# HotStick.net
KiCad netlist of a schematic drawn in EAGLE
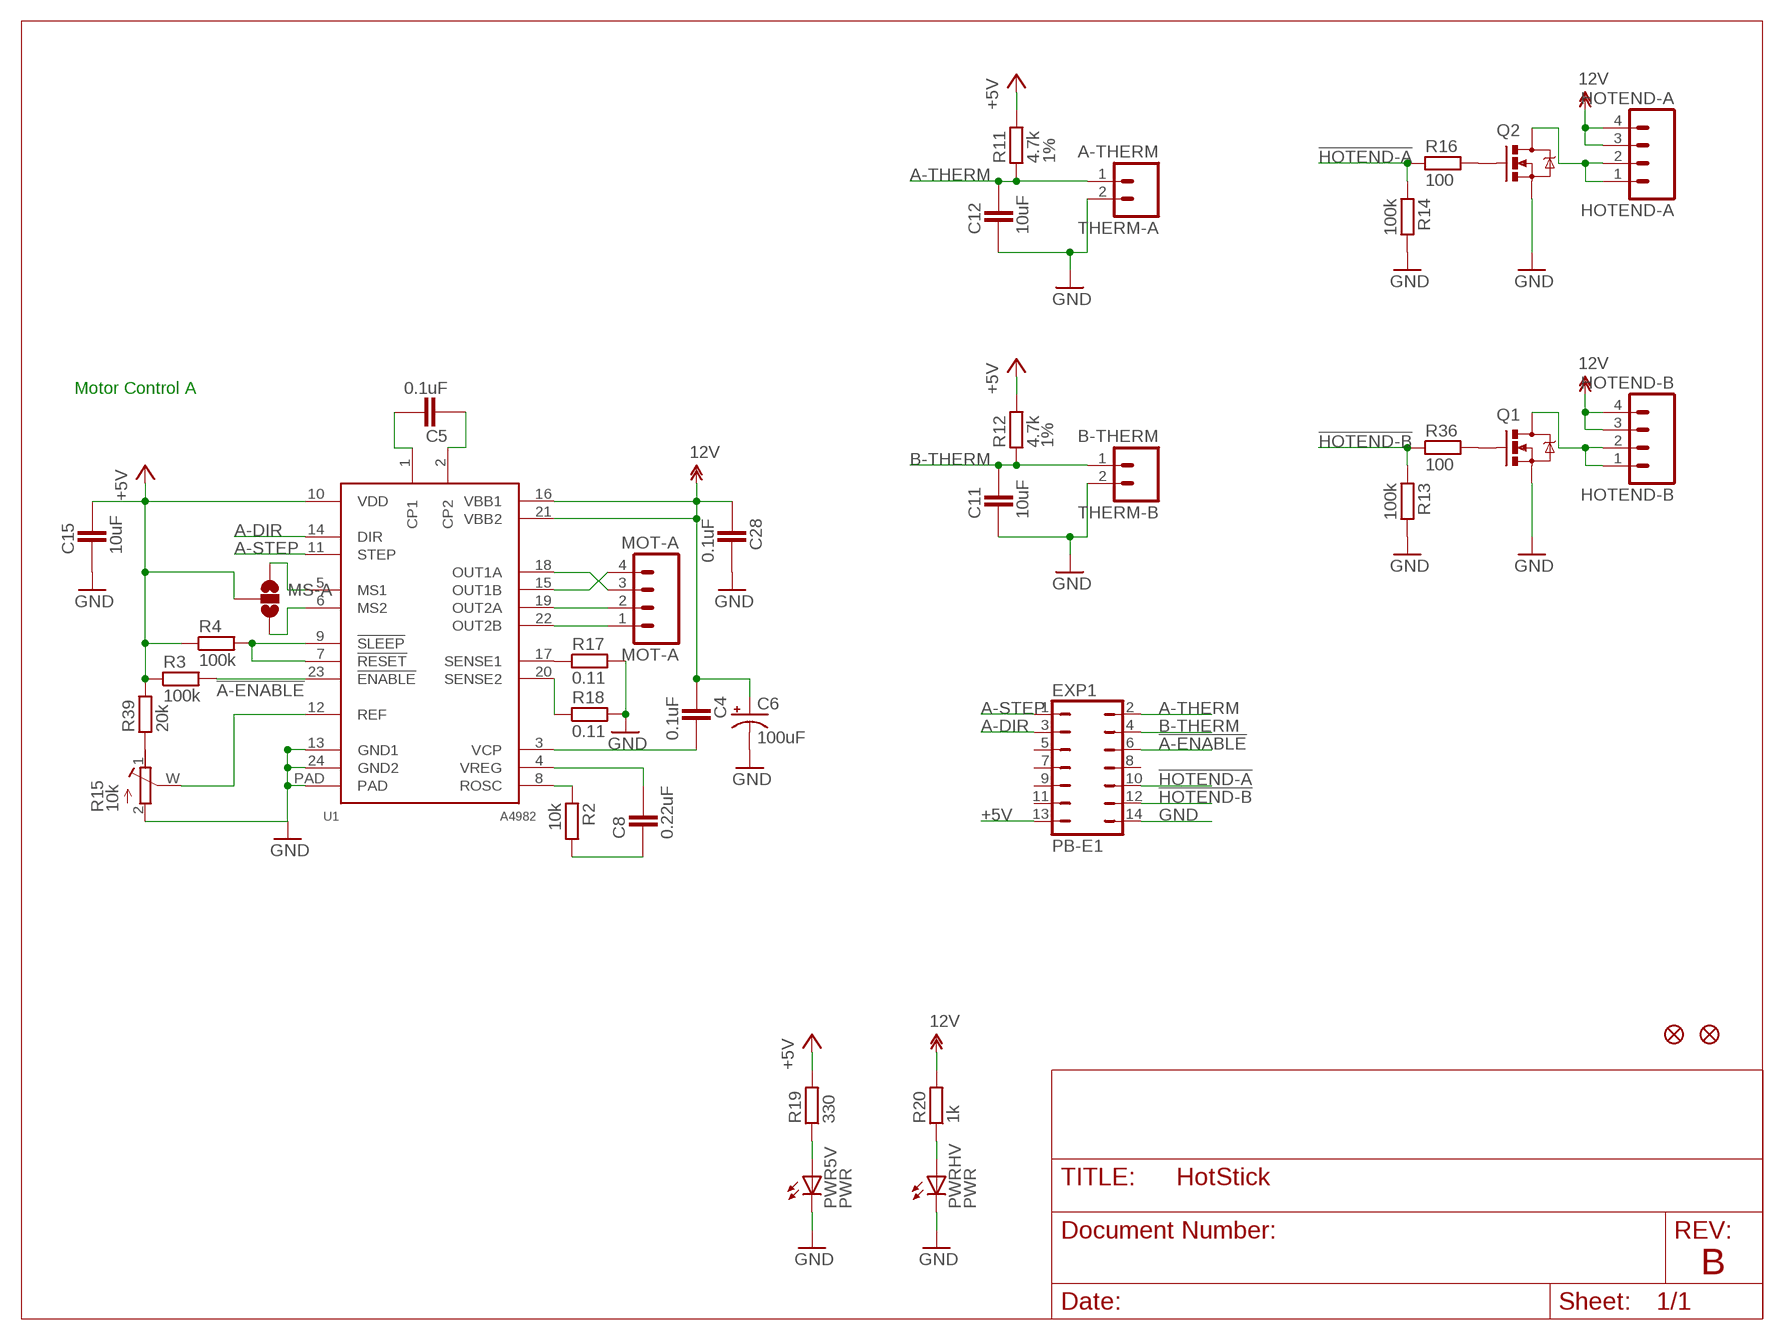
[diagram p0: schematic, sheet 1]

(export (version "E")
  (design (tool "Eeschema 10.0.6"))
  (components
    (comp (ref "C4")
      (value "0.1uF")
      (footprint "eagle-import:CAPC2012X145AN")
      (libsource (lib "eagle-import") (part "CAPACITOR_0805"))
    )
    (comp (ref "C5")
      (value "0.1uF")
      (footprint "eagle-import:CAPC2012X145AN")
      (libsource (lib "eagle-import") (part "CAPACITOR_0805"))
    )
    (comp (ref "C6")
      (value "100uF")
      (footprint "eagle-import:PANASONIC_D")
      (libsource (lib "eagle-import") (part "CPOL-USD"))
    )
    (comp (ref "C8")
      (value "0.22uF")
      (footprint "eagle-import:CAPC2012X145AN")
      (libsource (lib "eagle-import") (part "CAPACITOR_0805"))
    )
    (comp (ref "C11")
      (value "10uF")
      (footprint "eagle-import:CAPC2012X145AN")
      (libsource (lib "eagle-import") (part "CAPACITOR_0805"))
    )
    (comp (ref "C12")
      (value "10uF")
      (footprint "eagle-import:CAPC2012X145AN")
      (libsource (lib "eagle-import") (part "CAPACITOR_0805"))
    )
    (comp (ref "C15")
      (value "10uF")
      (footprint "eagle-import:CAPC2012X145AN")
      (libsource (lib "eagle-import") (part "CAPACITOR_0805"))
    )
    (comp (ref "C28")
      (value "0.1uF")
      (footprint "eagle-import:CAPC2012X145AN")
      (libsource (lib "eagle-import") (part "CAPACITOR_0805"))
    )
    (comp (ref "EXP1")
      (value "PB-E1")
      (footprint "eagle-import:JP7Q")
      (libsource (lib "eagle-import") (part "JP7Q"))
    )
    (comp (ref "HOTEND-A")
      (value "HOTEND-A")
      (footprint "eagle-import:MOLEX-1X4")
      (libsource (lib "eagle-import") (part "M04POLAR"))
    )
    (comp (ref "HOTEND-B")
      (value "HOTEND-B")
      (footprint "eagle-import:MOLEX-1X4")
      (libsource (lib "eagle-import") (part "M04POLAR"))
    )
    (comp (ref "JP1")
      (value "FIDUCIAL1X2.5")
      (footprint "eagle-import:FIDUCIAL-1X2.5")
      (libsource (lib "eagle-import") (part "FIDUCIAL1X2.5"))
    )
    (comp (ref "JP2")
      (value "FIDUCIAL1X2.5")
      (footprint "eagle-import:FIDUCIAL-1X2.5")
      (libsource (lib "eagle-import") (part "FIDUCIAL1X2.5"))
    )
    (comp (ref "MOT-A")
      (value "MOT-A")
      (footprint "eagle-import:MOLEX-1X4")
      (libsource (lib "eagle-import") (part "M04POLAR"))
    )
    (comp (ref "MS-A")
      (value "SOLDERJUMPER_2WAYCONNECTED")
      (footprint "eagle-import:SJ_3_CONNECTED")
      (libsource (lib "eagle-import") (part "SOLDERJUMPER_2WAYCONNECTED"))
    )
    (comp (ref "PWR5V")
      (value "PWR")
      (footprint "eagle-import:CHIP-LED0805")
      (libsource (lib "eagle-import") (part "LEDCHIP-LED0805"))
    )
    (comp (ref "PWRHV")
      (value "PWR")
      (footprint "eagle-import:CHIP-LED0805")
      (libsource (lib "eagle-import") (part "LEDCHIP-LED0805"))
    )
    (comp (ref "Q1")
      (value "MOSFET-NCHANNELPTH2")
      (footprint "eagle-import:TO220V")
      (libsource (lib "eagle-import") (part "MOSFET-NCHANNELPTH2"))
    )
    (comp (ref "Q2")
      (value "MOSFET-NCHANNELPTH2")
      (footprint "eagle-import:TO220V")
      (libsource (lib "eagle-import") (part "MOSFET-NCHANNELPTH2"))
    )
    (comp (ref "R2")
      (value "10k")
      (footprint "eagle-import:RESC2012X70N")
      (libsource (lib "eagle-import") (part "RESISTOR_0805"))
    )
    (comp (ref "R3")
      (value "100k")
      (footprint "eagle-import:RESC2012X70N")
      (libsource (lib "eagle-import") (part "RESISTOR_0805"))
    )
    (comp (ref "R4")
      (value "100k")
      (footprint "eagle-import:RESC2012X70N")
      (libsource (lib "eagle-import") (part "RESISTOR_0805"))
    )
    (comp (ref "R11")
      (value "4.7k")
      (footprint "eagle-import:RESC2012X70N")
      (fields (field (name "TOLERANCE") "1%"))
      (libsource (lib "eagle-import") (part "RESISTOR_0805"))
    )
    (comp (ref "R12")
      (value "4.7k")
      (footprint "eagle-import:RESC2012X70N")
      (fields (field (name "TOLERANCE") "1%"))
      (libsource (lib "eagle-import") (part "RESISTOR_0805"))
    )
    (comp (ref "R13")
      (value "100k")
      (footprint "eagle-import:RESC2012X70N")
      (libsource (lib "eagle-import") (part "RESISTOR_0805"))
    )
    (comp (ref "R14")
      (value "100k")
      (footprint "eagle-import:RESC2012X70N")
      (libsource (lib "eagle-import") (part "RESISTOR_0805"))
    )
    (comp (ref "R15")
      (value "10k")
      (footprint "eagle-import:RTRIM-ST4ETB")
      (libsource (lib "eagle-import") (part "RTRIM-ST-4EA"))
    )
    (comp (ref "R16")
      (value "100")
      (footprint "eagle-import:RESC2012X70N")
      (libsource (lib "eagle-import") (part "RESISTOR_0805"))
    )
    (comp (ref "R17")
      (value "0.11")
      (footprint "eagle-import:RESC2012X70N")
      (libsource (lib "eagle-import") (part "RESISTOR_0805"))
    )
    (comp (ref "R18")
      (value "0.11")
      (footprint "eagle-import:RESC2012X70N")
      (libsource (lib "eagle-import") (part "RESISTOR_0805"))
    )
    (comp (ref "R19")
      (value "330")
      (footprint "eagle-import:RESC2012X70N")
      (libsource (lib "eagle-import") (part "RESISTOR_0805"))
    )
    (comp (ref "R20")
      (value "1k")
      (footprint "eagle-import:RESC2012X70N")
      (libsource (lib "eagle-import") (part "RESISTOR_0805"))
    )
    (comp (ref "R36")
      (value "100")
      (footprint "eagle-import:RESC2012X70N")
      (libsource (lib "eagle-import") (part "RESISTOR_0805"))
    )
    (comp (ref "R39")
      (value "20k")
      (footprint "eagle-import:RESC2012X70N")
      (libsource (lib "eagle-import") (part "RESISTOR_0805"))
    )
    (comp (ref "THERM-A")
      (value "A-THERM")
      (footprint "eagle-import:1X02")
      (libsource (lib "eagle-import") (part "M02PTH"))
    )
    (comp (ref "THERM-B")
      (value "B-THERM")
      (footprint "eagle-import:1X02")
      (libsource (lib "eagle-import") (part "M02PTH"))
    )
    (comp (ref "U1")
      (value "A4982")
      (footprint "eagle-import:TSSOP-24")
      (libsource (lib "eagle-import") (part "A4982"))
    )
  )
  (nets
    (net (code "1") (name "+5V") (class "Default")
      (node (ref "C15") (pin "2") (pinfunction "2_2") (pintype "passive"))
      (node (ref "EXP1") (pin "13") (pinfunction "13_13") (pintype "passive"))
      (node (ref "MS-A") (pin "2") (pinfunction "2_2") (pintype "passive"))
      (node (ref "R11") (pin "2") (pinfunction "2_2") (pintype "passive"))
      (node (ref "R12") (pin "2") (pinfunction "2_2") (pintype "passive"))
      (node (ref "R19") (pin "2") (pinfunction "2_2") (pintype "passive"))
      (node (ref "R3") (pin "1") (pinfunction "1_1") (pintype "passive"))
      (node (ref "R39") (pin "2") (pinfunction "2_2") (pintype "passive"))
      (node (ref "R4") (pin "1") (pinfunction "1_1") (pintype "passive"))
      (node (ref "U1") (pin "10") (pinfunction "VDD_10") (pintype "power_in"))
    )
    (net (code "2") (name "/A-DIR") (class "Default")
      (node (ref "EXP1") (pin "3") (pinfunction "3_3") (pintype "passive"))
      (node (ref "U1") (pin "14") (pinfunction "DIR_14") (pintype "input"))
    )
    (net (code "3") (name "/A-STEP") (class "Default")
      (node (ref "EXP1") (pin "1") (pinfunction "1_1") (pintype "passive"))
      (node (ref "U1") (pin "11") (pinfunction "STEP_11") (pintype "input"))
    )
    (net (code "4") (name "/A-THERM") (class "Default")
      (node (ref "C12") (pin "2") (pinfunction "2_2") (pintype "passive"))
      (node (ref "EXP1") (pin "2") (pinfunction "2_2") (pintype "passive"))
      (node (ref "R11") (pin "1") (pinfunction "1_1") (pintype "passive"))
      (node (ref "THERM-A") (pin "1") (pinfunction "1_1") (pintype "passive"))
    )
    (net (code "5") (name "/B-THERM") (class "Default")
      (node (ref "C11") (pin "2") (pinfunction "2_2") (pintype "passive"))
      (node (ref "EXP1") (pin "4") (pinfunction "4_4") (pintype "passive"))
      (node (ref "R12") (pin "1") (pinfunction "1_1") (pintype "passive"))
      (node (ref "THERM-B") (pin "1") (pinfunction "1_1") (pintype "passive"))
    )
    (net (code "6") (name "/~{A-ENABLE}") (class "Default")
      (node (ref "EXP1") (pin "6") (pinfunction "6_6") (pintype "passive"))
      (node (ref "R3") (pin "2") (pinfunction "2_2") (pintype "passive"))
      (node (ref "U1") (pin "23") (pinfunction "~{ENABLE}_23") (pintype "input"))
    )
    (net (code "7") (name "/~{HOTEND-A}") (class "Default")
      (node (ref "EXP1") (pin "10") (pinfunction "10_10") (pintype "passive"))
      (node (ref "R14") (pin "1") (pinfunction "1_1") (pintype "passive"))
      (node (ref "R16") (pin "1") (pinfunction "1_1") (pintype "passive"))
    )
    (net (code "8") (name "/~{HOTEND-B}") (class "Default")
      (node (ref "EXP1") (pin "12") (pinfunction "12_12") (pintype "passive"))
      (node (ref "R13") (pin "1") (pinfunction "1_1") (pintype "passive"))
      (node (ref "R36") (pin "1") (pinfunction "1_1") (pintype "passive"))
    )
    (net (code "9") (name "12V") (class "Default")
      (node (ref "C28") (pin "1") (pinfunction "1_1") (pintype "passive"))
      (node (ref "C4") (pin "1") (pinfunction "1_1") (pintype "passive"))
      (node (ref "C6") (pin "+") (pinfunction "+_+") (pintype "passive"))
      (node (ref "HOTEND-A") (pin "3") (pinfunction "3_3") (pintype "passive"))
      (node (ref "HOTEND-A") (pin "4") (pinfunction "4_4") (pintype "passive"))
      (node (ref "HOTEND-B") (pin "3") (pinfunction "3_3") (pintype "passive"))
      (node (ref "HOTEND-B") (pin "4") (pinfunction "4_4") (pintype "passive"))
      (node (ref "R20") (pin "2") (pinfunction "2_2") (pintype "passive"))
      (node (ref "U1") (pin "16") (pinfunction "VBB1_16") (pintype "power_in"))
      (node (ref "U1") (pin "21") (pinfunction "VBB2_21") (pintype "power_in"))
    )
    (net (code "10") (name "GND") (class "Default")
      (node (ref "C11") (pin "1") (pinfunction "1_1") (pintype "passive"))
      (node (ref "C12") (pin "1") (pinfunction "1_1") (pintype "passive"))
      (node (ref "C15") (pin "1") (pinfunction "1_1") (pintype "passive"))
      (node (ref "C28") (pin "2") (pinfunction "2_2") (pintype "passive"))
      (node (ref "C6") (pin "-") (pinfunction "-_-") (pintype "passive"))
      (node (ref "EXP1") (pin "14") (pinfunction "14_14") (pintype "passive"))
      (node (ref "PWR5V") (pin "C") (pinfunction "C_C") (pintype "passive"))
      (node (ref "PWRHV") (pin "C") (pinfunction "C_C") (pintype "passive"))
      (node (ref "Q1") (pin "3") (pinfunction "S_3") (pintype "passive"))
      (node (ref "Q2") (pin "3") (pinfunction "S_3") (pintype "passive"))
      (node (ref "R13") (pin "2") (pinfunction "2_2") (pintype "passive"))
      (node (ref "R14") (pin "2") (pinfunction "2_2") (pintype "passive"))
      (node (ref "R15") (pin "2") (pinfunction "E_2") (pintype "passive"))
      (node (ref "R17") (pin "2") (pinfunction "2_2") (pintype "passive"))
      (node (ref "R18") (pin "2") (pinfunction "2_2") (pintype "passive"))
      (node (ref "THERM-A") (pin "2") (pinfunction "2_2") (pintype "passive"))
      (node (ref "THERM-B") (pin "2") (pinfunction "2_2") (pintype "passive"))
      (node (ref "U1") (pin "13") (pinfunction "GND1_13") (pintype "power_in"))
      (node (ref "U1") (pin "24") (pinfunction "GND2_24") (pintype "power_in"))
      (node (ref "U1") (pin "PAD") (pinfunction "PAD_PAD") (pintype "power_in"))
    )
    (net (code "11") (name "Net-(C8-Pad1)") (class "Default")
      (node (ref "C8") (pin "1") (pinfunction "1_1") (pintype "passive"))
      (node (ref "R2") (pin "2") (pinfunction "2_2") (pintype "passive"))
    )
    (net (code "12") (name "Net-(PWR5V-PadA)") (class "Default")
      (node (ref "PWR5V") (pin "A") (pinfunction "A_A") (pintype "passive"))
      (node (ref "R19") (pin "1") (pinfunction "1_1") (pintype "passive"))
    )
    (net (code "13") (name "Net-(PWRHV-PadA)") (class "Default")
      (node (ref "PWRHV") (pin "A") (pinfunction "A_A") (pintype "passive"))
      (node (ref "R20") (pin "1") (pinfunction "1_1") (pintype "passive"))
    )
    (net (code "14") (name "Net-(Q1-D)") (class "Default")
      (node (ref "HOTEND-B") (pin "1") (pinfunction "1_1") (pintype "passive"))
      (node (ref "HOTEND-B") (pin "2") (pinfunction "2_2") (pintype "passive"))
      (node (ref "Q1") (pin "2") (pinfunction "D_2") (pintype "passive"))
    )
    (net (code "15") (name "Net-(Q1-G)") (class "Default")
      (node (ref "Q1") (pin "1") (pinfunction "G_1") (pintype "passive"))
      (node (ref "R36") (pin "2") (pinfunction "2_2") (pintype "passive"))
    )
    (net (code "16") (name "Net-(Q2-D)") (class "Default")
      (node (ref "HOTEND-A") (pin "1") (pinfunction "1_1") (pintype "passive"))
      (node (ref "HOTEND-A") (pin "2") (pinfunction "2_2") (pintype "passive"))
      (node (ref "Q2") (pin "2") (pinfunction "D_2") (pintype "passive"))
    )
    (net (code "17") (name "Net-(Q2-G)") (class "Default")
      (node (ref "Q2") (pin "1") (pinfunction "G_1") (pintype "passive"))
      (node (ref "R16") (pin "2") (pinfunction "2_2") (pintype "passive"))
    )
    (net (code "18") (name "Net-(R15-A)") (class "Default")
      (node (ref "R15") (pin "1") (pinfunction "A_1") (pintype "passive"))
      (node (ref "R39") (pin "1") (pinfunction "1_1") (pintype "passive"))
    )
    (net (code "19") (name "Net-(R15-S)") (class "Default")
      (node (ref "R15") (pin "W") (pinfunction "S_W") (pintype "passive"))
      (node (ref "U1") (pin "12") (pinfunction "REF_12") (pintype "input"))
    )
    (net (code "20") (name "Net-(U1-CP1)") (class "Default")
      (node (ref "C5") (pin "2") (pinfunction "2_2") (pintype "passive"))
      (node (ref "U1") (pin "1") (pinfunction "CP1_1") (pintype "passive"))
    )
    (net (code "21") (name "Net-(U1-CP2)") (class "Default")
      (node (ref "C5") (pin "1") (pinfunction "1_1") (pintype "passive"))
      (node (ref "U1") (pin "2") (pinfunction "CP2_2") (pintype "passive"))
    )
    (net (code "22") (name "Net-(U1-MS1)") (class "Default")
      (node (ref "MS-A") (pin "1") (pinfunction "1_1") (pintype "passive"))
      (node (ref "U1") (pin "5") (pinfunction "MS1_5") (pintype "input"))
    )
    (net (code "23") (name "Net-(U1-MS2)") (class "Default")
      (node (ref "MS-A") (pin "3") (pinfunction "3_3") (pintype "passive"))
      (node (ref "U1") (pin "6") (pinfunction "MS2_6") (pintype "input"))
    )
    (net (code "24") (name "Net-(U1-OUT1A)") (class "Default")
      (node (ref "MOT-A") (pin "3") (pinfunction "3_3") (pintype "passive"))
      (node (ref "U1") (pin "18") (pinfunction "OUT1A_18") (pintype "output"))
    )
    (net (code "25") (name "Net-(U1-OUT1B)") (class "Default")
      (node (ref "MOT-A") (pin "4") (pinfunction "4_4") (pintype "passive"))
      (node (ref "U1") (pin "15") (pinfunction "OUT1B_15") (pintype "output"))
    )
    (net (code "26") (name "Net-(U1-OUT2A)") (class "Default")
      (node (ref "MOT-A") (pin "2") (pinfunction "2_2") (pintype "passive"))
      (node (ref "U1") (pin "19") (pinfunction "OUT2A_19") (pintype "output"))
    )
    (net (code "27") (name "Net-(U1-OUT2B)") (class "Default")
      (node (ref "MOT-A") (pin "1") (pinfunction "1_1") (pintype "passive"))
      (node (ref "U1") (pin "22") (pinfunction "OUT2B_22") (pintype "output"))
    )
    (net (code "28") (name "Net-(U1-ROSC)") (class "Default")
      (node (ref "R2") (pin "1") (pinfunction "1_1") (pintype "passive"))
      (node (ref "U1") (pin "8") (pinfunction "ROSC_8") (pintype "passive"))
    )
    (net (code "29") (name "Net-(U1-SENSE1)") (class "Default")
      (node (ref "R17") (pin "1") (pinfunction "1_1") (pintype "passive"))
      (node (ref "U1") (pin "17") (pinfunction "SENSE1_17") (pintype "passive"))
    )
    (net (code "30") (name "Net-(U1-SENSE2)") (class "Default")
      (node (ref "R18") (pin "1") (pinfunction "1_1") (pintype "passive"))
      (node (ref "U1") (pin "20") (pinfunction "SENSE2_20") (pintype "passive"))
    )
    (net (code "31") (name "Net-(U1-VCP)") (class "Default")
      (node (ref "C4") (pin "2") (pinfunction "2_2") (pintype "passive"))
      (node (ref "U1") (pin "3") (pinfunction "VCP_3") (pintype "passive"))
    )
    (net (code "32") (name "Net-(U1-VREG)") (class "Default")
      (node (ref "C8") (pin "2") (pinfunction "2_2") (pintype "passive"))
      (node (ref "U1") (pin "4") (pinfunction "VREG_4") (pintype "passive"))
    )
    (net (code "33") (name "Net-(U1-~{RESET})") (class "Default")
      (node (ref "R4") (pin "2") (pinfunction "2_2") (pintype "passive"))
      (node (ref "U1") (pin "7") (pinfunction "~{RESET}_7") (pintype "input"))
      (node (ref "U1") (pin "9") (pinfunction "~{SLEEP}_9") (pintype "input"))
    )
    (net (code "34") (name "unconnected-(EXP1-Pad5)") (class "Default")
      (node (ref "EXP1") (pin "5") (pinfunction "5_5") (pintype "passive"))
    )
    (net (code "35") (name "unconnected-(EXP1-Pad7)") (class "Default")
      (node (ref "EXP1") (pin "7") (pinfunction "7_7") (pintype "passive"))
    )
    (net (code "36") (name "unconnected-(EXP1-Pad8)") (class "Default")
      (node (ref "EXP1") (pin "8") (pinfunction "8_8") (pintype "passive"))
    )
    (net (code "37") (name "unconnected-(EXP1-Pad9)") (class "Default")
      (node (ref "EXP1") (pin "9") (pinfunction "9_9") (pintype "passive"))
    )
    (net (code "38") (name "unconnected-(EXP1-Pad11)") (class "Default")
      (node (ref "EXP1") (pin "11") (pinfunction "11_11") (pintype "passive"))
    )
  )
)
